# IOs.net
KiCad netlist of a schematic drawn in Altium Designer
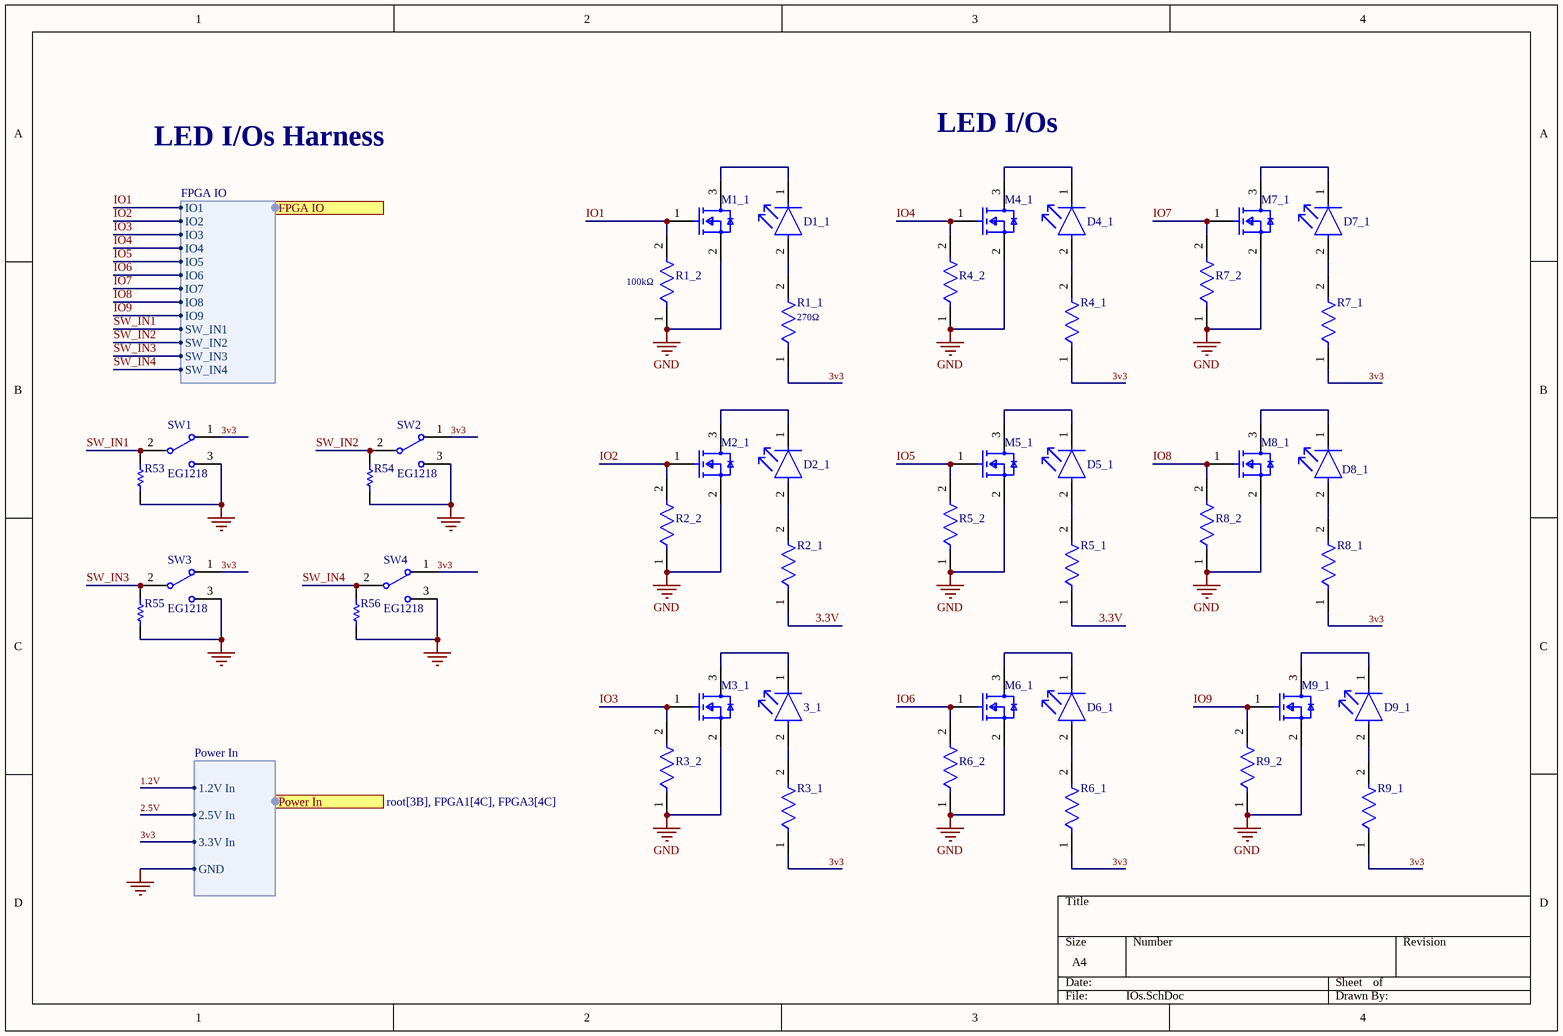
[diagram p0: IOs.SchDoc]

(export (version "E")
  (design (tool "Eeschema 10.0.6"))
  (components
    (comp (ref "3_1")
      (value "LW T6SH.CB-CZEY-FK0PM0-Z664")
      (footprint "FP-LW_T6SH_CB-CZEY-FK0PM0-MFG")
      (description "TOPLED")
      (libsource (lib "Altium Content Vault") (part "f19a1b30ec2e0e83542a893ae8c56fc"))
    )
    (comp (ref "D1_1")
      (value "LW T6SH.CB-CZEY-FK0PM0-Z664")
      (footprint "FP-LW_T6SH_CB-CZEY-FK0PM0-MFG")
      (description "TOPLED")
      (libsource (lib "Altium Content Vault") (part "f19a1b30ec2e0e83542a893ae8c56fc"))
    )
    (comp (ref "D2_1")
      (value "LW T6SH.CB-CZEY-FK0PM0-Z664")
      (footprint "FP-LW_T6SH_CB-CZEY-FK0PM0-MFG")
      (description "TOPLED")
      (libsource (lib "Altium Content Vault") (part "f19a1b30ec2e0e83542a893ae8c56fc"))
    )
    (comp (ref "D4_1")
      (value "LW T6SH.CB-CZEY-FK0PM0-Z664")
      (footprint "FP-LW_T6SH_CB-CZEY-FK0PM0-MFG")
      (description "TOPLED")
      (libsource (lib "Altium Content Vault") (part "f19a1b30ec2e0e83542a893ae8c56fc"))
    )
    (comp (ref "D5_1")
      (value "LW T6SH.CB-CZEY-FK0PM0-Z664")
      (footprint "FP-LW_T6SH_CB-CZEY-FK0PM0-MFG")
      (description "TOPLED")
      (libsource (lib "Altium Content Vault") (part "f19a1b30ec2e0e83542a893ae8c56fc"))
    )
    (comp (ref "D6_1")
      (value "LW T6SH.CB-CZEY-FK0PM0-Z664")
      (footprint "FP-LW_T6SH_CB-CZEY-FK0PM0-MFG")
      (description "TOPLED")
      (libsource (lib "Altium Content Vault") (part "f19a1b30ec2e0e83542a893ae8c56fc"))
    )
    (comp (ref "D7_1")
      (value "LW T6SH.CB-CZEY-FK0PM0-Z664")
      (footprint "FP-LW_T6SH_CB-CZEY-FK0PM0-MFG")
      (description "TOPLED")
      (libsource (lib "Altium Content Vault") (part "f19a1b30ec2e0e83542a893ae8c56fc"))
    )
    (comp (ref "D8_1")
      (value "LW T6SH.CB-CZEY-FK0PM0-Z664")
      (footprint "FP-LW_T6SH_CB-CZEY-FK0PM0-MFG")
      (description "TOPLED")
      (libsource (lib "Altium Content Vault") (part "f19a1b30ec2e0e83542a893ae8c56fc"))
    )
    (comp (ref "D9_1")
      (value "LW T6SH.CB-CZEY-FK0PM0-Z664")
      (footprint "FP-LW_T6SH_CB-CZEY-FK0PM0-MFG")
      (description "TOPLED")
      (libsource (lib "Altium Content Vault") (part "f19a1b30ec2e0e83542a893ae8c56fc"))
    )
    (comp (ref "M1_1")
      (value "SI2342DS-T1-GE3")
      (footprint "FP-S-03946-MFG")
      (description "MOSFET N-CH 8V 6A SOT-23")
      (fields
        (field (name "OCTOPART") "https://octopart.com/si2342ds-t1-ge3-vishay-45050957")
        (field (name "MANUFACTURER") "Vishay")
      )
      (libsource (lib "Altium Content Vault") (part "1661867509f36a4ffa577829538a895"))
    )
    (comp (ref "M2_1")
      (value "SI2342DS-T1-GE3")
      (footprint "FP-S-03946-MFG")
      (description "MOSFET N-CH 8V 6A SOT-23")
      (fields
        (field (name "OCTOPART") "https://octopart.com/si2342ds-t1-ge3-vishay-45050957")
        (field (name "MANUFACTURER") "Vishay")
      )
      (libsource (lib "Altium Content Vault") (part "1661867509f36a4ffa577829538a895"))
    )
    (comp (ref "M3_1")
      (value "SI2342DS-T1-GE3")
      (footprint "FP-S-03946-MFG")
      (description "MOSFET N-CH 8V 6A SOT-23")
      (fields
        (field (name "OCTOPART") "https://octopart.com/si2342ds-t1-ge3-vishay-45050957")
        (field (name "MANUFACTURER") "Vishay")
      )
      (libsource (lib "Altium Content Vault") (part "1661867509f36a4ffa577829538a895"))
    )
    (comp (ref "M4_1")
      (value "SI2342DS-T1-GE3")
      (footprint "FP-S-03946-MFG")
      (description "MOSFET N-CH 8V 6A SOT-23")
      (fields
        (field (name "OCTOPART") "https://octopart.com/si2342ds-t1-ge3-vishay-45050957")
        (field (name "MANUFACTURER") "Vishay")
      )
      (libsource (lib "Altium Content Vault") (part "1661867509f36a4ffa577829538a895"))
    )
    (comp (ref "M5_1")
      (value "SI2342DS-T1-GE3")
      (footprint "FP-S-03946-MFG")
      (description "MOSFET N-CH 8V 6A SOT-23")
      (fields
        (field (name "OCTOPART") "https://octopart.com/si2342ds-t1-ge3-vishay-45050957")
        (field (name "MANUFACTURER") "Vishay")
      )
      (libsource (lib "Altium Content Vault") (part "1661867509f36a4ffa577829538a895"))
    )
    (comp (ref "M6_1")
      (value "SI2342DS-T1-GE3")
      (footprint "FP-S-03946-MFG")
      (description "MOSFET N-CH 8V 6A SOT-23")
      (fields
        (field (name "OCTOPART") "https://octopart.com/si2342ds-t1-ge3-vishay-45050957")
        (field (name "MANUFACTURER") "Vishay")
      )
      (libsource (lib "Altium Content Vault") (part "1661867509f36a4ffa577829538a895"))
    )
    (comp (ref "M7_1")
      (value "SI2342DS-T1-GE3")
      (footprint "FP-S-03946-MFG")
      (description "MOSFET N-CH 8V 6A SOT-23")
      (fields
        (field (name "OCTOPART") "https://octopart.com/si2342ds-t1-ge3-vishay-45050957")
        (field (name "MANUFACTURER") "Vishay")
      )
      (libsource (lib "Altium Content Vault") (part "1661867509f36a4ffa577829538a895"))
    )
    (comp (ref "M8_1")
      (value "SI2342DS-T1-GE3")
      (footprint "FP-S-03946-MFG")
      (description "MOSFET N-CH 8V 6A SOT-23")
      (fields
        (field (name "OCTOPART") "https://octopart.com/si2342ds-t1-ge3-vishay-45050957")
        (field (name "MANUFACTURER") "Vishay")
      )
      (libsource (lib "Altium Content Vault") (part "1661867509f36a4ffa577829538a895"))
    )
    (comp (ref "M9_1")
      (value "SI2342DS-T1-GE3")
      (footprint "FP-S-03946-MFG")
      (description "MOSFET N-CH 8V 6A SOT-23")
      (fields
        (field (name "OCTOPART") "https://octopart.com/si2342ds-t1-ge3-vishay-45050957")
        (field (name "MANUFACTURER") "Vishay")
      )
      (libsource (lib "Altium Content Vault") (part "1661867509f36a4ffa577829538a895"))
    )
    (comp (ref "R1_1")
      (value "270Ω")
      (footprint "FP-CR0402-IPC_A")
      (description "Thick Film Chip Resistors 0402 270Ω 0.0625W 5% 200ppm/°C")
      (fields (field (name "TOLERANCE") "5%"))
      (libsource (lib "Altium Content Vault") (part "1029c3af85768c4190bb7ad29bc67b5"))
    )
    (comp (ref "R1_2")
      (value "100kΩ")
      (footprint "FP-TFCR0402-IPC_B")
      (description "RES Thin Film,  100kΩ, 0.5%, 0.063W, 25ppm/°C, 0402")
      (libsource (lib "Altium Content Vault") (part "1029c3af85768c4190bb7ad29bc67b5"))
    )
    (comp (ref "R2_1")
      (value "CR0402-JW-271GLF")
      (footprint "FP-CR0402-IPC_A")
      (description "Thick Film Chip Resistors 0402 270Ω 0.0625W 5% 200ppm/°C")
      (fields (field (name "TOLERANCE") "5%"))
      (libsource (lib "Altium Content Vault") (part "1029c3af85768c4190bb7ad29bc67b5"))
    )
    (comp (ref "R2_2")
      (value "100kΩ")
      (footprint "FP-TFCR0402-IPC_B")
      (description "RES Thin Film,  100kΩ, 0.5%, 0.063W, 25ppm/°C, 0402")
      (libsource (lib "Altium Content Vault") (part "1029c3af85768c4190bb7ad29bc67b5"))
    )
    (comp (ref "R3_1")
      (value "CR0402-JW-271GLF")
      (footprint "FP-CR0402-IPC_A")
      (description "Thick Film Chip Resistors 0402 270Ω 0.0625W 5% 200ppm/°C")
      (fields (field (name "TOLERANCE") "5%"))
      (libsource (lib "Altium Content Vault") (part "1029c3af85768c4190bb7ad29bc67b5"))
    )
    (comp (ref "R3_2")
      (value "100kΩ")
      (footprint "FP-TFCR0402-IPC_B")
      (description "RES Thin Film,  100kΩ, 0.5%, 0.063W, 25ppm/°C, 0402")
      (libsource (lib "Altium Content Vault") (part "1029c3af85768c4190bb7ad29bc67b5"))
    )
    (comp (ref "R4_1")
      (value "CR0402-JW-271GLF")
      (footprint "FP-CR0402-IPC_A")
      (description "Thick Film Chip Resistors 0402 270Ω 0.0625W 5% 200ppm/°C")
      (fields (field (name "TOLERANCE") "5%"))
      (libsource (lib "Altium Content Vault") (part "1029c3af85768c4190bb7ad29bc67b5"))
    )
    (comp (ref "R4_2")
      (value "100kΩ")
      (footprint "FP-TFCR0402-IPC_B")
      (description "RES Thin Film,  100kΩ, 0.5%, 0.063W, 25ppm/°C, 0402")
      (libsource (lib "Altium Content Vault") (part "1029c3af85768c4190bb7ad29bc67b5"))
    )
    (comp (ref "R5_1")
      (value "CR0402-JW-271GLF")
      (footprint "FP-CR0402-IPC_A")
      (description "Thick Film Chip Resistors 0402 270Ω 0.0625W 5% 200ppm/°C")
      (fields (field (name "TOLERANCE") "5%"))
      (libsource (lib "Altium Content Vault") (part "1029c3af85768c4190bb7ad29bc67b5"))
    )
    (comp (ref "R5_2")
      (value "100kΩ")
      (footprint "FP-TFCR0402-IPC_B")
      (description "RES Thin Film,  100kΩ, 0.5%, 0.063W, 25ppm/°C, 0402")
      (libsource (lib "Altium Content Vault") (part "1029c3af85768c4190bb7ad29bc67b5"))
    )
    (comp (ref "R6_1")
      (value "CR0402-JW-271GLF")
      (footprint "FP-CR0402-IPC_A")
      (description "Thick Film Chip Resistors 0402 270Ω 0.0625W 5% 200ppm/°C")
      (fields (field (name "TOLERANCE") "5%"))
      (libsource (lib "Altium Content Vault") (part "1029c3af85768c4190bb7ad29bc67b5"))
    )
    (comp (ref "R6_2")
      (value "100kΩ")
      (footprint "FP-TFCR0402-IPC_B")
      (description "RES Thin Film,  100kΩ, 0.5%, 0.063W, 25ppm/°C, 0402")
      (libsource (lib "Altium Content Vault") (part "1029c3af85768c4190bb7ad29bc67b5"))
    )
    (comp (ref "R7_1")
      (value "CR0402-JW-271GLF")
      (footprint "FP-CR0402-IPC_A")
      (description "Thick Film Chip Resistors 0402 270Ω 0.0625W 5% 200ppm/°C")
      (fields (field (name "TOLERANCE") "5%"))
      (libsource (lib "Altium Content Vault") (part "1029c3af85768c4190bb7ad29bc67b5"))
    )
    (comp (ref "R7_2")
      (value "100kΩ")
      (footprint "FP-TFCR0402-IPC_B")
      (description "RES Thin Film,  100kΩ, 0.5%, 0.063W, 25ppm/°C, 0402")
      (libsource (lib "Altium Content Vault") (part "1029c3af85768c4190bb7ad29bc67b5"))
    )
    (comp (ref "R8_1")
      (value "CR0402-JW-271GLF")
      (footprint "FP-CR0402-IPC_A")
      (description "Thick Film Chip Resistors 0402 270Ω 0.0625W 5% 200ppm/°C")
      (fields (field (name "TOLERANCE") "5%"))
      (libsource (lib "Altium Content Vault") (part "1029c3af85768c4190bb7ad29bc67b5"))
    )
    (comp (ref "R8_2")
      (value "100kΩ")
      (footprint "FP-TFCR0402-IPC_B")
      (description "RES Thin Film,  100kΩ, 0.5%, 0.063W, 25ppm/°C, 0402")
      (libsource (lib "Altium Content Vault") (part "1029c3af85768c4190bb7ad29bc67b5"))
    )
    (comp (ref "R9_1")
      (value "CR0402-JW-271GLF")
      (footprint "FP-CR0402-IPC_A")
      (description "Thick Film Chip Resistors 0402 270Ω 0.0625W 5% 200ppm/°C")
      (fields (field (name "TOLERANCE") "5%"))
      (libsource (lib "Altium Content Vault") (part "1029c3af85768c4190bb7ad29bc67b5"))
    )
    (comp (ref "R9_2")
      (value "100kΩ")
      (footprint "FP-TFCR0402-IPC_B")
      (description "RES Thin Film,  100kΩ, 0.5%, 0.063W, 25ppm/°C, 0402")
      (libsource (lib "Altium Content Vault") (part "1029c3af85768c4190bb7ad29bc67b5"))
    )
    (comp (ref "R53")
      (value "3K3 5% 0603(1608)")
      (footprint "RESC0603(1608)_N")
      (description "3K3 0.1W 5% 0603 (1608 Metric)  SMD")
      (fields (field (name "TOLERANCE") "5 %") (field (name "POWER") "0.1 W"))
      (libsource (lib "Altium Content Vault") (part "RES"))
    )
    (comp (ref "R54")
      (value "3K3 5% 0603(1608)")
      (footprint "RESC0603(1608)_N")
      (description "3K3 0.1W 5% 0603 (1608 Metric)  SMD")
      (fields (field (name "TOLERANCE") "5 %") (field (name "POWER") "0.1 W"))
      (libsource (lib "Altium Content Vault") (part "RES"))
    )
    (comp (ref "R55")
      (value "3K3 5% 0603(1608)")
      (footprint "RESC0603(1608)_N")
      (description "3K3 0.1W 5% 0603 (1608 Metric)  SMD")
      (fields (field (name "TOLERANCE") "5 %") (field (name "POWER") "0.1 W"))
      (libsource (lib "Altium Content Vault") (part "RES"))
    )
    (comp (ref "R56")
      (value "3K3 5% 0603(1608)")
      (footprint "RESC0603(1608)_N")
      (description "3K3 0.1W 5% 0603 (1608 Metric)  SMD")
      (fields (field (name "TOLERANCE") "5 %") (field (name "POWER") "0.1 W"))
      (libsource (lib "Altium Content Vault") (part "RES"))
    )
    (comp (ref "SW1")
      (value "EG1218")
      (footprint "ESWI-EG1218_V")
      (description "Slide Switch, 500 V, -20 to 70 degC, 3-Pin THD, RoHS")
      (libsource (lib "Altium Content Vault") (part "SW-SPDT-3_B"))
    )
    (comp (ref "SW2")
      (value "EG1218")
      (footprint "ESWI-EG1218_V")
      (description "Slide Switch, 500 V, -20 to 70 degC, 3-Pin THD, RoHS")
      (libsource (lib "Altium Content Vault") (part "SW-SPDT-3_B"))
    )
    (comp (ref "SW3")
      (value "EG1218")
      (footprint "ESWI-EG1218_V")
      (description "Slide Switch, 500 V, -20 to 70 degC, 3-Pin THD, RoHS")
      (libsource (lib "Altium Content Vault") (part "SW-SPDT-3_B"))
    )
    (comp (ref "SW4")
      (value "EG1218")
      (footprint "ESWI-EG1218_V")
      (description "Slide Switch, 500 V, -20 to 70 degC, 3-Pin THD, RoHS")
      (libsource (lib "Altium Content Vault") (part "SW-SPDT-3_B"))
    )
  )
  (nets
    (net (code "7") (name "/3.3V") (class "Default")
      (node (ref "R2_1") (pin "1") (pinfunction "1_1") (pintype "passive"))
      (node (ref "R5_1") (pin "1") (pinfunction "1_1") (pintype "passive"))
    )
    (net (code "8") (name "/3v3") (class "Default")
      (node (ref "R1_1") (pin "1") (pinfunction "1_1") (pintype "passive"))
      (node (ref "R3_1") (pin "1") (pinfunction "1_1") (pintype "passive"))
      (node (ref "R4_1") (pin "1") (pinfunction "1_1") (pintype "passive"))
      (node (ref "R6_1") (pin "1") (pinfunction "1_1") (pintype "passive"))
      (node (ref "R7_1") (pin "1") (pinfunction "1_1") (pintype "passive"))
      (node (ref "R8_1") (pin "1") (pinfunction "1_1") (pintype "passive"))
      (node (ref "R9_1") (pin "1") (pinfunction "1_1") (pintype "passive"))
      (node (ref "SW1") (pin "1") (pinfunction "1_1") (pintype "passive"))
      (node (ref "SW2") (pin "1") (pinfunction "1_1") (pintype "passive"))
      (node (ref "SW3") (pin "1") (pinfunction "1_1") (pintype "passive"))
      (node (ref "SW4") (pin "1") (pinfunction "1_1") (pintype "passive"))
    )
    (net (code "9") (name "/IO1") (class "Default")
      (node (ref "M1_1") (pin "1") (pinfunction "G_1") (pintype "passive"))
      (node (ref "R1_2") (pin "2") (pinfunction "2_2") (pintype "passive"))
    )
    (net (code "10") (name "/IO2") (class "Default")
      (node (ref "M2_1") (pin "1") (pinfunction "G_1") (pintype "passive"))
      (node (ref "R2_2") (pin "2") (pinfunction "2_2") (pintype "passive"))
    )
    (net (code "11") (name "/IO3") (class "Default")
      (node (ref "M3_1") (pin "1") (pinfunction "G_1") (pintype "passive"))
      (node (ref "R3_2") (pin "2") (pinfunction "2_2") (pintype "passive"))
    )
    (net (code "12") (name "/IO4") (class "Default")
      (node (ref "M4_1") (pin "1") (pinfunction "G_1") (pintype "passive"))
      (node (ref "R4_2") (pin "2") (pinfunction "2_2") (pintype "passive"))
    )
    (net (code "13") (name "/IO5") (class "Default")
      (node (ref "M5_1") (pin "1") (pinfunction "G_1") (pintype "passive"))
      (node (ref "R5_2") (pin "2") (pinfunction "2_2") (pintype "passive"))
    )
    (net (code "14") (name "/IO6") (class "Default")
      (node (ref "M6_1") (pin "1") (pinfunction "G_1") (pintype "passive"))
      (node (ref "R6_2") (pin "2") (pinfunction "2_2") (pintype "passive"))
    )
    (net (code "15") (name "/IO7") (class "Default")
      (node (ref "M7_1") (pin "1") (pinfunction "G_1") (pintype "passive"))
      (node (ref "R7_2") (pin "2") (pinfunction "2_2") (pintype "passive"))
    )
    (net (code "16") (name "/IO8") (class "Default")
      (node (ref "M8_1") (pin "1") (pinfunction "G_1") (pintype "passive"))
      (node (ref "R8_2") (pin "2") (pinfunction "2_2") (pintype "passive"))
    )
    (net (code "17") (name "/IO9") (class "Default")
      (node (ref "M9_1") (pin "1") (pinfunction "G_1") (pintype "passive"))
      (node (ref "R9_2") (pin "2") (pinfunction "2_2") (pintype "passive"))
    )
    (net (code "18") (name "/SW_IN1") (class "Default")
      (node (ref "R53") (pin "2") (pinfunction "2_2") (pintype "passive"))
      (node (ref "SW1") (pin "2") (pinfunction "COM_2") (pintype "passive"))
    )
    (net (code "19") (name "/SW_IN2") (class "Default")
      (node (ref "R54") (pin "2") (pinfunction "2_2") (pintype "passive"))
      (node (ref "SW2") (pin "2") (pinfunction "COM_2") (pintype "passive"))
    )
    (net (code "20") (name "/SW_IN3") (class "Default")
      (node (ref "R55") (pin "2") (pinfunction "2_2") (pintype "passive"))
      (node (ref "SW3") (pin "2") (pinfunction "COM_2") (pintype "passive"))
    )
    (net (code "21") (name "/SW_IN4") (class "Default")
      (node (ref "R56") (pin "2") (pinfunction "2_2") (pintype "passive"))
      (node (ref "SW4") (pin "2") (pinfunction "COM_2") (pintype "passive"))
    )
    (net (code "24") (name "GND") (class "Default")
      (node (ref "M1_1") (pin "2") (pinfunction "S_2") (pintype "passive"))
      (node (ref "M2_1") (pin "2") (pinfunction "S_2") (pintype "passive"))
      (node (ref "M3_1") (pin "2") (pinfunction "S_2") (pintype "passive"))
      (node (ref "M4_1") (pin "2") (pinfunction "S_2") (pintype "passive"))
      (node (ref "M5_1") (pin "2") (pinfunction "S_2") (pintype "passive"))
      (node (ref "M6_1") (pin "2") (pinfunction "S_2") (pintype "passive"))
      (node (ref "M7_1") (pin "2") (pinfunction "S_2") (pintype "passive"))
      (node (ref "M8_1") (pin "2") (pinfunction "S_2") (pintype "passive"))
      (node (ref "M9_1") (pin "2") (pinfunction "S_2") (pintype "passive"))
      (node (ref "R1_2") (pin "1") (pinfunction "1_1") (pintype "passive"))
      (node (ref "R2_2") (pin "1") (pinfunction "1_1") (pintype "passive"))
      (node (ref "R3_2") (pin "1") (pinfunction "1_1") (pintype "passive"))
      (node (ref "R4_2") (pin "1") (pinfunction "1_1") (pintype "passive"))
      (node (ref "R53") (pin "1") (pinfunction "1_1") (pintype "passive"))
      (node (ref "R54") (pin "1") (pinfunction "1_1") (pintype "passive"))
      (node (ref "R55") (pin "1") (pinfunction "1_1") (pintype "passive"))
      (node (ref "R56") (pin "1") (pinfunction "1_1") (pintype "passive"))
      (node (ref "R5_2") (pin "1") (pinfunction "1_1") (pintype "passive"))
      (node (ref "R6_2") (pin "1") (pinfunction "1_1") (pintype "passive"))
      (node (ref "R7_2") (pin "1") (pinfunction "1_1") (pintype "passive"))
      (node (ref "R8_2") (pin "1") (pinfunction "1_1") (pintype "passive"))
      (node (ref "R9_2") (pin "1") (pinfunction "1_1") (pintype "passive"))
      (node (ref "SW1") (pin "3") (pinfunction "3_3") (pintype "passive"))
      (node (ref "SW2") (pin "3") (pinfunction "3_3") (pintype "passive"))
      (node (ref "SW3") (pin "3") (pinfunction "3_3") (pintype "passive"))
      (node (ref "SW4") (pin "3") (pinfunction "3_3") (pintype "passive"))
    )
    (net (code "25") (name "Net-(3_1-A)") (class "Default")
      (node (ref "3_1") (pin "2") (pinfunction "A_2") (pintype "passive"))
      (node (ref "R3_1") (pin "2") (pinfunction "2_2") (pintype "passive"))
    )
    (net (code "26") (name "Net-(3_1-C)") (class "Default")
      (node (ref "3_1") (pin "1") (pinfunction "C_1") (pintype "passive"))
      (node (ref "M3_1") (pin "3") (pinfunction "D_3") (pintype "passive"))
    )
    (net (code "27") (name "Net-(D1_1-A)") (class "Default")
      (node (ref "D1_1") (pin "2") (pinfunction "A_2") (pintype "passive"))
      (node (ref "R1_1") (pin "2") (pinfunction "2_2") (pintype "passive"))
    )
    (net (code "28") (name "Net-(D1_1-C)") (class "Default")
      (node (ref "D1_1") (pin "1") (pinfunction "C_1") (pintype "passive"))
      (node (ref "M1_1") (pin "3") (pinfunction "D_3") (pintype "passive"))
    )
    (net (code "29") (name "Net-(D2_1-A)") (class "Default")
      (node (ref "D2_1") (pin "2") (pinfunction "A_2") (pintype "passive"))
      (node (ref "R2_1") (pin "2") (pinfunction "2_2") (pintype "passive"))
    )
    (net (code "30") (name "Net-(D2_1-C)") (class "Default")
      (node (ref "D2_1") (pin "1") (pinfunction "C_1") (pintype "passive"))
      (node (ref "M2_1") (pin "3") (pinfunction "D_3") (pintype "passive"))
    )
    (net (code "31") (name "Net-(D4_1-A)") (class "Default")
      (node (ref "D4_1") (pin "2") (pinfunction "A_2") (pintype "passive"))
      (node (ref "R4_1") (pin "2") (pinfunction "2_2") (pintype "passive"))
    )
    (net (code "32") (name "Net-(D4_1-C)") (class "Default")
      (node (ref "D4_1") (pin "1") (pinfunction "C_1") (pintype "passive"))
      (node (ref "M4_1") (pin "3") (pinfunction "D_3") (pintype "passive"))
    )
    (net (code "33") (name "Net-(D5_1-A)") (class "Default")
      (node (ref "D5_1") (pin "2") (pinfunction "A_2") (pintype "passive"))
      (node (ref "R5_1") (pin "2") (pinfunction "2_2") (pintype "passive"))
    )
    (net (code "34") (name "Net-(D5_1-C)") (class "Default")
      (node (ref "D5_1") (pin "1") (pinfunction "C_1") (pintype "passive"))
      (node (ref "M5_1") (pin "3") (pinfunction "D_3") (pintype "passive"))
    )
    (net (code "35") (name "Net-(D6_1-A)") (class "Default")
      (node (ref "D6_1") (pin "2") (pinfunction "A_2") (pintype "passive"))
      (node (ref "R6_1") (pin "2") (pinfunction "2_2") (pintype "passive"))
    )
    (net (code "36") (name "Net-(D6_1-C)") (class "Default")
      (node (ref "D6_1") (pin "1") (pinfunction "C_1") (pintype "passive"))
      (node (ref "M6_1") (pin "3") (pinfunction "D_3") (pintype "passive"))
    )
    (net (code "37") (name "Net-(D7_1-A)") (class "Default")
      (node (ref "D7_1") (pin "2") (pinfunction "A_2") (pintype "passive"))
      (node (ref "R7_1") (pin "2") (pinfunction "2_2") (pintype "passive"))
    )
    (net (code "38") (name "Net-(D7_1-C)") (class "Default")
      (node (ref "D7_1") (pin "1") (pinfunction "C_1") (pintype "passive"))
      (node (ref "M7_1") (pin "3") (pinfunction "D_3") (pintype "passive"))
    )
    (net (code "39") (name "Net-(D8_1-A)") (class "Default")
      (node (ref "D8_1") (pin "2") (pinfunction "A_2") (pintype "passive"))
      (node (ref "R8_1") (pin "2") (pinfunction "2_2") (pintype "passive"))
    )
    (net (code "40") (name "Net-(D8_1-C)") (class "Default")
      (node (ref "D8_1") (pin "1") (pinfunction "C_1") (pintype "passive"))
      (node (ref "M8_1") (pin "3") (pinfunction "D_3") (pintype "passive"))
    )
    (net (code "41") (name "Net-(D9_1-A)") (class "Default")
      (node (ref "D9_1") (pin "2") (pinfunction "A_2") (pintype "passive"))
      (node (ref "R9_1") (pin "2") (pinfunction "2_2") (pintype "passive"))
    )
    (net (code "42") (name "Net-(D9_1-C)") (class "Default")
      (node (ref "D9_1") (pin "1") (pinfunction "C_1") (pintype "passive"))
      (node (ref "M9_1") (pin "3") (pinfunction "D_3") (pintype "passive"))
    )
  )
)
